# 2.net
KiCad netlist of a schematic drawn in Altium Designer
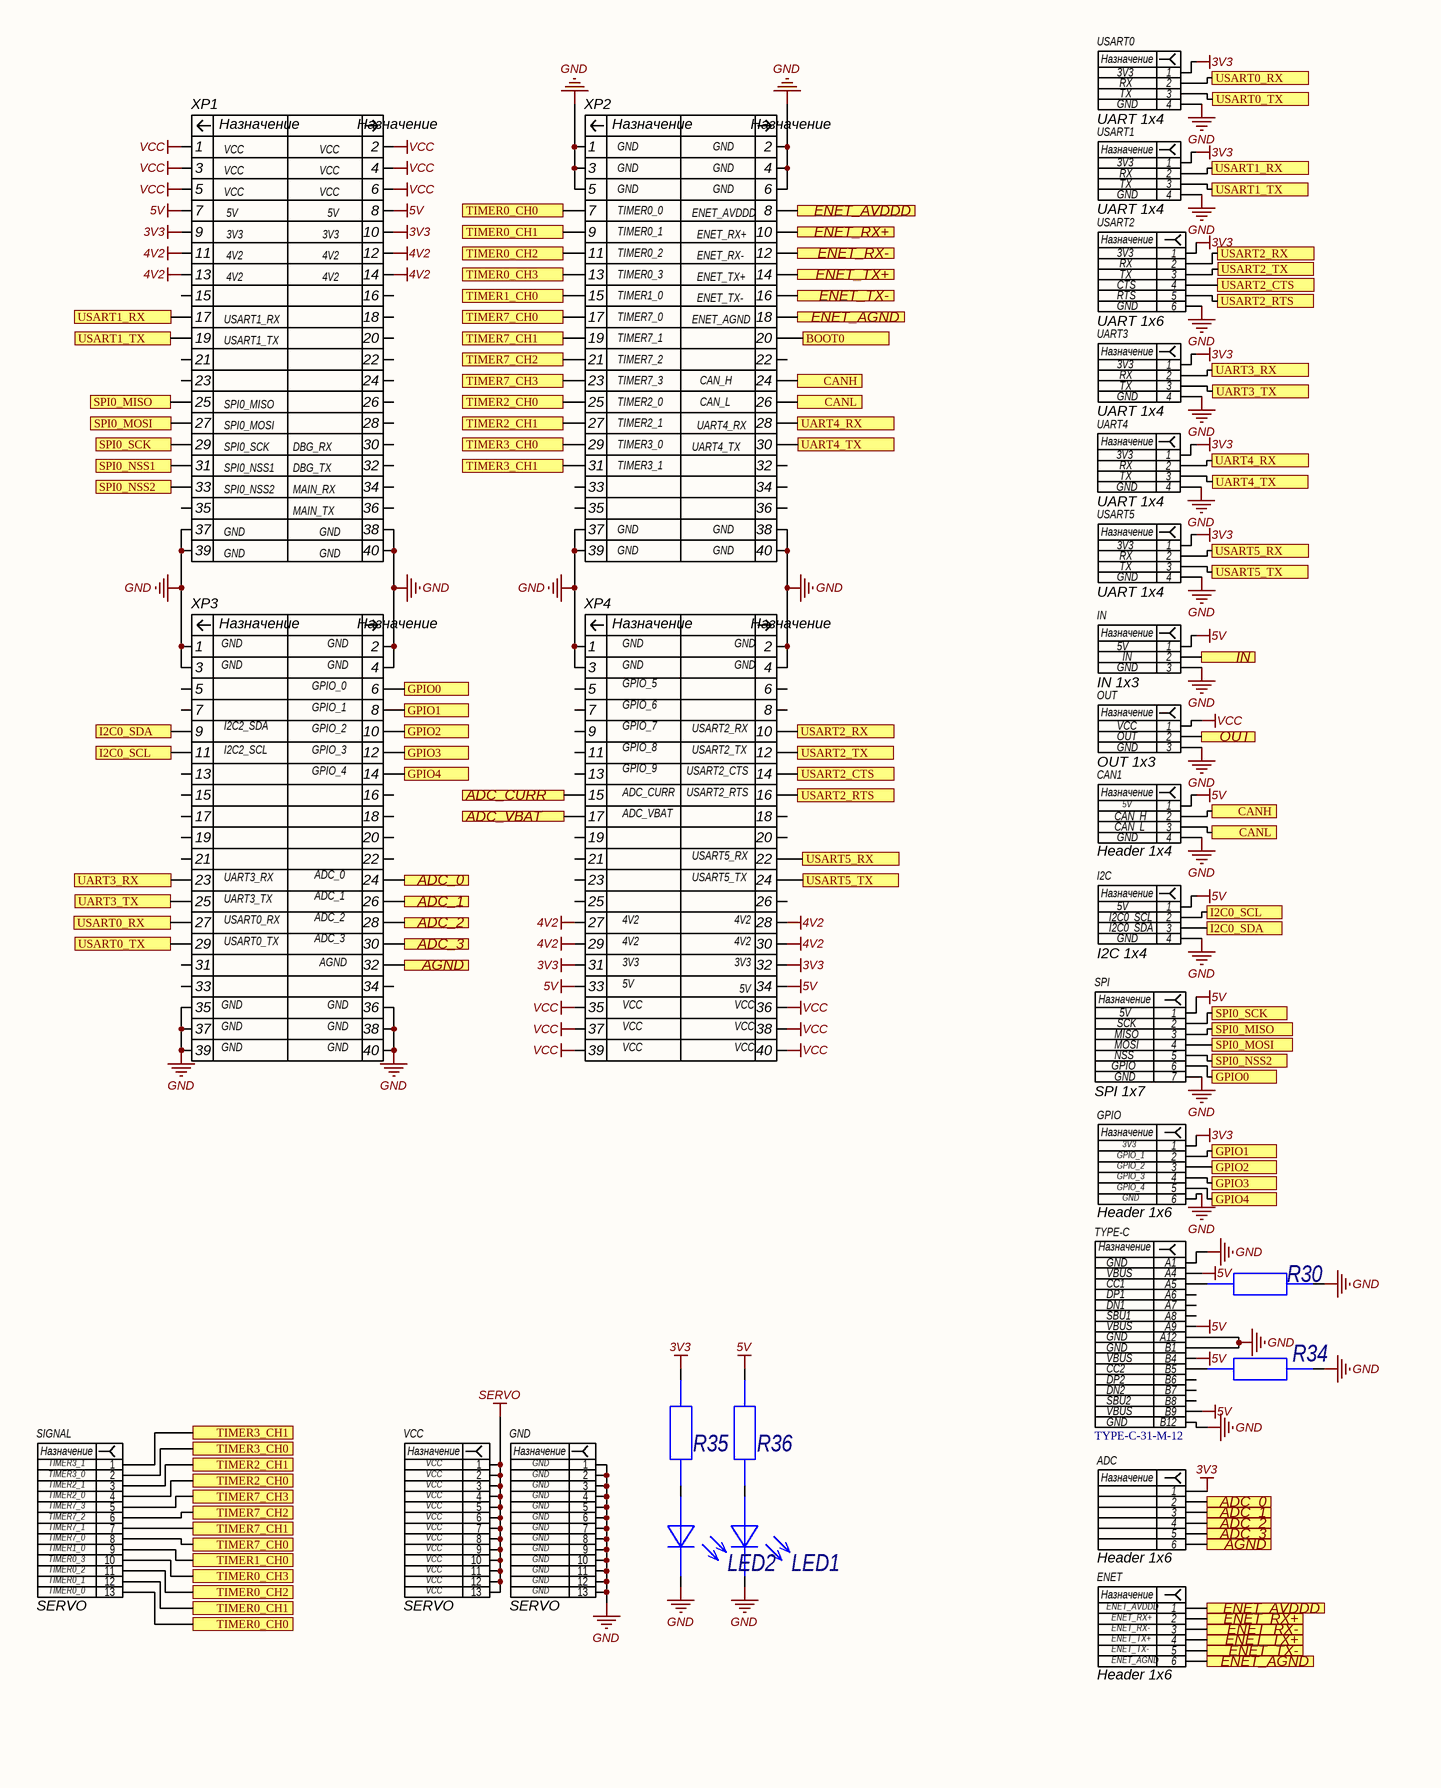
[diagram p0: нижняя плата версия 2.SchDoc, left]
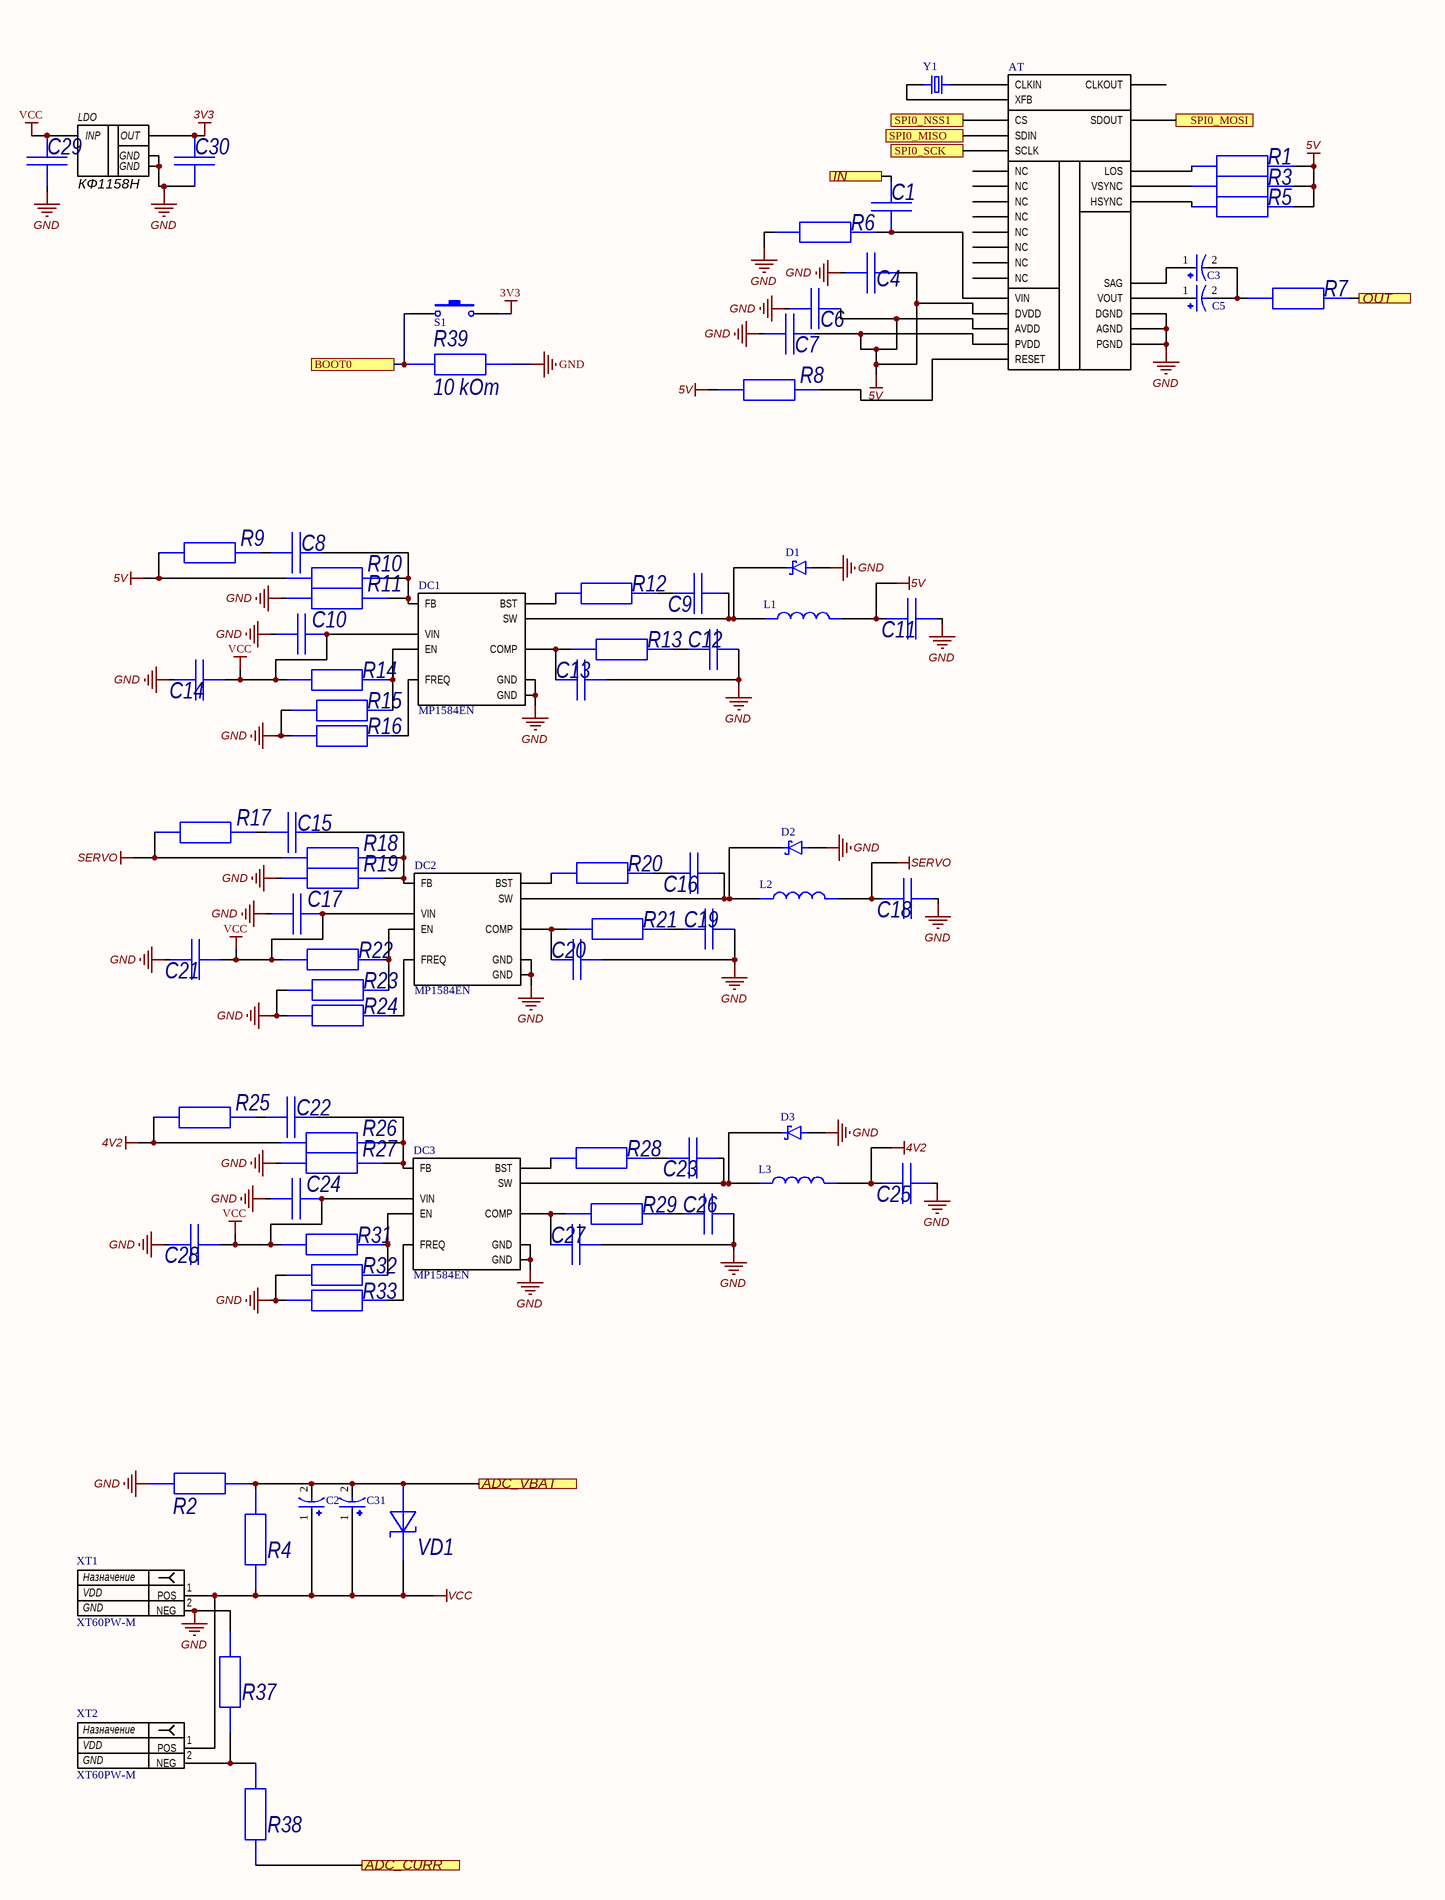
[diagram p1: нижняя плата версия 2.SchDoc, right]

(export (version "E")
  (design (tool "Eeschema 10.0.6"))
  (components
    (comp (ref "ADC")
      (value "Header 1x6")
      (footprint "PicoBlade 6pin")
      (libsource (lib "полётный контроллер") (part "Header 1x6"))
    )
    (comp (ref "AT")
      (value "AT7456")
      (footprint "at7456")
      (description "OSD")
      (libsource (lib "полётный контроллер") (part "AT7456"))
    )
    (comp (ref "C1")
      (value "Capacitor")
      (footprint "C0603")
      (fields (field (name "PUBLISHER") "Andrew Danich"))
      (libsource (lib "Capacitor GOST") (part "Capacitor"))
    )
    (comp (ref "C2")
      (value "T493B105K025BC6120")
      (footprint "CAPPM3528X210N")
      (description "Tantalum Surface Mount Capacitors")
      (fields (field (name "MF") "KEMET"))
      (libsource (lib "T493B105K025BC6120") (part "T493B105K025BC6120"))
    )
    (comp (ref "C3")
      (value "T493B105K025BC6120")
      (footprint "CAPPM3528X210N")
      (description "Tantalum Surface Mount Capacitors")
      (fields (field (name "MF") "KEMET"))
      (libsource (lib "") (part "T493B105K025BC6120_1"))
    )
    (comp (ref "C4")
      (value "Capacitor")
      (footprint "C0603")
      (fields (field (name "PUBLISHER") "Andrew Danich"))
      (libsource (lib "Capacitor GOST") (part "Capacitor"))
    )
    (comp (ref "C5")
      (value "T493B105K025BC6120")
      (footprint "CAPPM3528X210N")
      (description "Tantalum Surface Mount Capacitors")
      (fields (field (name "MF") "KEMET"))
      (libsource (lib "") (part "T493B105K025BC6120_1"))
    )
    (comp (ref "C6")
      (value "Capacitor")
      (footprint "C0603")
      (fields (field (name "PUBLISHER") "Andrew Danich"))
      (libsource (lib "Capacitor GOST") (part "Capacitor"))
    )
    (comp (ref "C7")
      (value "Capacitor")
      (footprint "C0603")
      (fields (field (name "PUBLISHER") "Andrew Danich"))
      (libsource (lib "Capacitor GOST") (part "Capacitor"))
    )
    (comp (ref "C8")
      (value "22 pF")
      (footprint "C0603")
      (fields (field (name "PUBLISHER") "Andrew Danich"))
      (libsource (lib "Capacitor GOST") (part "Capacitor"))
    )
    (comp (ref "C9")
      (value "0.1 uF")
      (footprint "C0603")
      (fields (field (name "PUBLISHER") "Andrew Danich"))
      (libsource (lib "Capacitor GOST") (part "Capacitor"))
    )
    (comp (ref "C10")
      (value "0.1 uF")
      (footprint "C0603")
      (fields (field (name "PUBLISHER") "Andrew Danich"))
      (libsource (lib "Capacitor GOST") (part "Capacitor"))
    )
    (comp (ref "C11")
      (value "22 uF")
      (footprint "C0603")
      (fields (field (name "PUBLISHER") "Andrew Danich"))
      (libsource (lib "Capacitor GOST") (part "Capacitor"))
    )
    (comp (ref "C12")
      (value "330 pF")
      (footprint "C0603")
      (fields (field (name "PUBLISHER") "Andrew Danich"))
      (libsource (lib "Capacitor GOST") (part "Capacitor"))
    )
    (comp (ref "C13")
      (value "1 pF")
      (footprint "C0603")
      (fields (field (name "PUBLISHER") "Andrew Danich"))
      (libsource (lib "Capacitor GOST") (part "Capacitor"))
    )
    (comp (ref "C14")
      (value "4.7 uF")
      (footprint "C0603")
      (fields (field (name "PUBLISHER") "Andrew Danich"))
      (libsource (lib "Capacitor GOST") (part "Capacitor"))
    )
    (comp (ref "C15")
      (value "22 pF")
      (footprint "C0603")
      (fields (field (name "PUBLISHER") "Andrew Danich"))
      (libsource (lib "Capacitor GOST") (part "Capacitor"))
    )
    (comp (ref "C16")
      (value "0.1 uF")
      (footprint "C0603")
      (fields (field (name "PUBLISHER") "Andrew Danich"))
      (libsource (lib "Capacitor GOST") (part "Capacitor"))
    )
    (comp (ref "C17")
      (value "0.1 uF")
      (footprint "C0603")
      (fields (field (name "PUBLISHER") "Andrew Danich"))
      (libsource (lib "Capacitor GOST") (part "Capacitor"))
    )
    (comp (ref "C18")
      (value "22 uF")
      (footprint "C0603")
      (fields (field (name "PUBLISHER") "Andrew Danich"))
      (libsource (lib "Capacitor GOST") (part "Capacitor"))
    )
    (comp (ref "C19")
      (value "330 pF")
      (footprint "C0603")
      (fields (field (name "PUBLISHER") "Andrew Danich"))
      (libsource (lib "Capacitor GOST") (part "Capacitor"))
    )
    (comp (ref "C20")
      (value "1 pF")
      (footprint "C0603")
      (fields (field (name "PUBLISHER") "Andrew Danich"))
      (libsource (lib "Capacitor GOST") (part "Capacitor"))
    )
    (comp (ref "C21")
      (value "4.7 uF")
      (footprint "C0603")
      (fields (field (name "PUBLISHER") "Andrew Danich"))
      (libsource (lib "Capacitor GOST") (part "Capacitor"))
    )
    (comp (ref "C22")
      (value "22 pF")
      (footprint "C0603")
      (fields (field (name "PUBLISHER") "Andrew Danich"))
      (libsource (lib "Capacitor GOST") (part "Capacitor"))
    )
    (comp (ref "C23")
      (value "0.1 uF")
      (footprint "C0603")
      (fields (field (name "PUBLISHER") "Andrew Danich"))
      (libsource (lib "Capacitor GOST") (part "Capacitor"))
    )
    (comp (ref "C24")
      (value "0.1 uF")
      (footprint "C0603")
      (fields (field (name "PUBLISHER") "Andrew Danich"))
      (libsource (lib "Capacitor GOST") (part "Capacitor"))
    )
    (comp (ref "C25")
      (value "33 uF")
      (footprint "C0603")
      (fields (field (name "PUBLISHER") "Andrew Danich"))
      (libsource (lib "Capacitor GOST") (part "Capacitor"))
    )
    (comp (ref "C26")
      (value "330 pF")
      (footprint "C0603")
      (fields (field (name "PUBLISHER") "Andrew Danich"))
      (libsource (lib "Capacitor GOST") (part "Capacitor"))
    )
    (comp (ref "C27")
      (value "2 pF")
      (footprint "C0603")
      (fields (field (name "PUBLISHER") "Andrew Danich"))
      (libsource (lib "Capacitor GOST") (part "Capacitor"))
    )
    (comp (ref "C28")
      (value "4.7 uF")
      (footprint "C0603")
      (fields (field (name "PUBLISHER") "Andrew Danich"))
      (libsource (lib "Capacitor GOST") (part "Capacitor"))
    )
    (comp (ref "C29")
      (value "0.1 uF")
      (footprint "C0603")
      (fields (field (name "PUBLISHER") "Andrew Danich"))
      (libsource (lib "Capacitor GOST") (part "Capacitor"))
    )
    (comp (ref "C30")
      (value "10 uF")
      (footprint "C0603")
      (fields (field (name "PUBLISHER") "Andrew Danich"))
      (libsource (lib "Capacitor GOST") (part "Capacitor"))
    )
    (comp (ref "C31")
      (value "T493B105K025BC6120")
      (footprint "CAPPM3528X210N")
      (description "Tantalum Surface Mount Capacitors")
      (fields (field (name "MF") "KEMET"))
      (libsource (lib "T493B105K025BC6120") (part "T493B105K025BC6120"))
    )
    (comp (ref "CAN1")
      (value "Header 1x4")
      (footprint "PicoBlade 4pin")
      (libsource (lib "полётный контроллер") (part "Header 1x4"))
    )
    (comp (ref "D1")
      (value "B340A-13-F")
      (footprint "DIOM5226X240N")
      (description "Diode, Rectifier, 3a, 40v, Do-214ac, Full Reel")
      (libsource (lib "B340A-13-F") (part "B340A-13-F"))
    )
    (comp (ref "D2")
      (value "B340A-13-F")
      (footprint "DIOM5226X240N")
      (description "Diode, Rectifier, 3a, 40v, Do-214ac, Full Reel")
      (libsource (lib "B340A-13-F") (part "B340A-13-F"))
    )
    (comp (ref "D3")
      (value "B340A-13-F")
      (footprint "DIOM5226X240N")
      (description "Diode, Rectifier, 3a, 40v, Do-214ac, Full Reel")
      (libsource (lib "B340A-13-F") (part "B340A-13-F"))
    )
    (comp (ref "DC1")
      (value "MP1584EN")
      (footprint "SOIC127P600X170-9N")
      (libsource (lib "полётный контроллер") (part "MP1584EN"))
    )
    (comp (ref "DC2")
      (value "MP1584EN")
      (footprint "SOIC127P600X170-9N")
      (libsource (lib "полётный контроллер") (part "MP1584EN"))
    )
    (comp (ref "DC3")
      (value "MP1584EN")
      (footprint "SOIC127P600X170-9N")
      (libsource (lib "полётный контроллер") (part "MP1584EN"))
    )
    (comp (ref "ENET")
      (value "Header 1x6")
      (footprint "PicoBlade 6pin")
      (libsource (lib "полётный контроллер") (part "Header 1x6"))
    )
    (comp (ref "GND")
      (value "SERVO")
      (footprint "SERV")
      (libsource (lib "полётный контроллер") (part "SERVO"))
    )
    (comp (ref "GPIO")
      (value "Header 1x6")
      (footprint "PicoBlade 6pin")
      (libsource (lib "полётный контроллер") (part "Header 1x6"))
    )
    (comp (ref "I2C")
      (value "I2C 1x4")
      (footprint "PicoBlade 4pin")
      (libsource (lib "полётный контроллер") (part "I2C 1x4"))
    )
    (comp (ref "IN")
      (value "IN 1x3")
      (footprint "PicoBlade 3pin")
      (libsource (lib "полётный контроллер") (part "IN 1x3"))
    )
    (comp (ref "L1")
      (value "12.3 uH")
      (footprint "IND_VLS6045EX-150M")
      (description "15 ÂµH Shielded Drum Core, Wirewound Inductor 2.5 A 75mOhm Nonstandard")
      (fields (field (name "MF") "TDK") (field (name "MP") "VLS6045EX-150M"))
      (libsource (lib "VLS6045EX-150M") (part "VLS6045EX-150M"))
    )
    (comp (ref "L2")
      (value "12.3 uH")
      (footprint "IND_VLS6045EX-150M")
      (description "15 ÂµH Shielded Drum Core, Wirewound Inductor 2.5 A 75mOhm Nonstandard")
      (fields (field (name "MF") "TDK") (field (name "MP") "VLS6045EX-150M"))
      (libsource (lib "VLS6045EX-150M") (part "VLS6045EX-150M"))
    )
    (comp (ref "L3")
      (value "12.3 uH")
      (footprint "IND_VLS6045EX-150M")
      (description "15 ÂµH Shielded Drum Core, Wirewound Inductor 2.5 A 75mOhm Nonstandard")
      (fields (field (name "MF") "TDK") (field (name "MP") "VLS6045EX-150M"))
      (libsource (lib "VLS6045EX-150M") (part "VLS6045EX-150M"))
    )
    (comp (ref "LDO")
      (value "КФ1158Н")
      (footprint "ТО-263")
      (libsource (lib "полётный контроллер") (part "КФ1158Н"))
    )
    (comp (ref "LED1")
      (value "Text")
      (footprint "LD0805")
      (fields (field (name "PUBLISHER") "Andrew Danich"))
      (libsource (lib "Led GOST") (part "Led-1"))
    )
    (comp (ref "LED2")
      (value "Text")
      (footprint "LD0805")
      (fields (field (name "PUBLISHER") "Andrew Danich"))
      (libsource (lib "Led GOST") (part "Led-1"))
    )
    (comp (ref "OUT")
      (value "OUT 1x3")
      (footprint "PicoBlade 3pin")
      (libsource (lib "полётный контроллер") (part "OUT 1x3"))
    )
    (comp (ref "R1")
      (value "1 kOm")
      (footprint "R0603")
      (fields (field (name "PUBLISHER") "Andrew Danich"))
      (libsource (lib "Resistor GOST") (part "Resistor"))
    )
    (comp (ref "R2")
      (value "~")
      (footprint "R0603")
      (fields (field (name "PUBLISHER") "Andrew Danich"))
      (libsource (lib "Resistor GOST") (part "Resistor"))
    )
    (comp (ref "R3")
      (value "1 kOm")
      (footprint "R0603")
      (fields (field (name "PUBLISHER") "Andrew Danich"))
      (libsource (lib "Resistor GOST") (part "Resistor"))
    )
    (comp (ref "R4")
      (value "~")
      (footprint "R0603")
      (fields (field (name "PUBLISHER") "Andrew Danich"))
      (libsource (lib "Resistor GOST") (part "Resistor"))
    )
    (comp (ref "R5")
      (value "1 kOm")
      (footprint "R0603")
      (fields (field (name "PUBLISHER") "Andrew Danich"))
      (libsource (lib "Resistor GOST") (part "Resistor"))
    )
    (comp (ref "R6")
      (value "10 kOm")
      (footprint "R0603")
      (fields (field (name "PUBLISHER") "Andrew Danich"))
      (libsource (lib "Resistor GOST") (part "Resistor"))
    )
    (comp (ref "R7")
      (value "10 kOm")
      (footprint "R0603")
      (fields (field (name "PUBLISHER") "Andrew Danich"))
      (libsource (lib "Resistor GOST") (part "Resistor"))
    )
    (comp (ref "R8")
      (value "10 kOm")
      (footprint "R0603")
      (fields (field (name "PUBLISHER") "Andrew Danich"))
      (libsource (lib "Resistor GOST") (part "Resistor"))
    )
    (comp (ref "R9")
      (value "0")
      (footprint "R0603")
      (fields (field (name "PUBLISHER") "Andrew Danich"))
      (libsource (lib "Resistor GOST") (part "Resistor"))
    )
    (comp (ref "R10")
      (value "124 kOm")
      (footprint "R0603")
      (fields (field (name "PUBLISHER") "Andrew Danich"))
      (libsource (lib "Resistor GOST") (part "Resistor"))
    )
    (comp (ref "R11")
      (value "23.7 kOm")
      (footprint "R0603")
      (fields (field (name "PUBLISHER") "Andrew Danich"))
      (libsource (lib "Resistor GOST") (part "Resistor"))
    )
    (comp (ref "R12")
      (value "0")
      (footprint "R0603")
      (fields (field (name "PUBLISHER") "Andrew Danich"))
      (libsource (lib "Resistor GOST") (part "Resistor"))
    )
    (comp (ref "R13")
      (value "76.8 kOm")
      (footprint "R0603")
      (fields (field (name "PUBLISHER") "Andrew Danich"))
      (libsource (lib "Resistor GOST") (part "Resistor"))
    )
    (comp (ref "R14")
      (value "100 kOm")
      (footprint "R0603")
      (fields (field (name "PUBLISHER") "Andrew Danich"))
      (libsource (lib "Resistor GOST") (part "Resistor"))
    )
    (comp (ref "R15")
      (value "18.7 kOm")
      (footprint "R0603")
      (fields (field (name "PUBLISHER") "Andrew Danich"))
      (libsource (lib "Resistor GOST") (part "Resistor"))
    )
    (comp (ref "R16")
      (value "193.38 kOm")
      (footprint "R0603")
      (fields (field (name "PUBLISHER") "Andrew Danich"))
      (libsource (lib "Resistor GOST") (part "Resistor"))
    )
    (comp (ref "R17")
      (value "0")
      (footprint "R0603")
      (fields (field (name "PUBLISHER") "Andrew Danich"))
      (libsource (lib "Resistor GOST") (part "Resistor"))
    )
    (comp (ref "R18")
      (value "124 kOm")
      (footprint "R0603")
      (fields (field (name "PUBLISHER") "Andrew Danich"))
      (libsource (lib "Resistor GOST") (part "Resistor"))
    )
    (comp (ref "R19")
      (value "23.7 kOm")
      (footprint "R0603")
      (fields (field (name "PUBLISHER") "Andrew Danich"))
      (libsource (lib "Resistor GOST") (part "Resistor"))
    )
    (comp (ref "R20")
      (value "0")
      (footprint "R0603")
      (fields (field (name "PUBLISHER") "Andrew Danich"))
      (libsource (lib "Resistor GOST") (part "Resistor"))
    )
    (comp (ref "R21")
      (value "76.8 kOm")
      (footprint "R0603")
      (fields (field (name "PUBLISHER") "Andrew Danich"))
      (libsource (lib "Resistor GOST") (part "Resistor"))
    )
    (comp (ref "R22")
      (value "100 kOm")
      (footprint "R0603")
      (fields (field (name "PUBLISHER") "Andrew Danich"))
      (libsource (lib "Resistor GOST") (part "Resistor"))
    )
    (comp (ref "R23")
      (value "18.7 kOm")
      (footprint "R0603")
      (fields (field (name "PUBLISHER") "Andrew Danich"))
      (libsource (lib "Resistor GOST") (part "Resistor"))
    )
    (comp (ref "R24")
      (value "193.38 kOm")
      (footprint "R0603")
      (fields (field (name "PUBLISHER") "Andrew Danich"))
      (libsource (lib "Resistor GOST") (part "Resistor"))
    )
    (comp (ref "R25")
      (value "0")
      (footprint "R0603")
      (fields (field (name "PUBLISHER") "Andrew Danich"))
      (libsource (lib "Resistor GOST") (part "Resistor"))
    )
    (comp (ref "R26")
      (value "124 kOm")
      (footprint "R0603")
      (fields (field (name "PUBLISHER") "Andrew Danich"))
      (libsource (lib "Resistor GOST") (part "Resistor"))
    )
    (comp (ref "R27")
      (value "29 kOm")
      (footprint "R0603")
      (fields (field (name "PUBLISHER") "Andrew Danich"))
      (libsource (lib "Resistor GOST") (part "Resistor"))
    )
    (comp (ref "R28")
      (value "0")
      (footprint "R0603")
      (fields (field (name "PUBLISHER") "Andrew Danich"))
      (libsource (lib "Resistor GOST") (part "Resistor"))
    )
    (comp (ref "R29")
      (value "100 kOm")
      (footprint "R0603")
      (fields (field (name "PUBLISHER") "Andrew Danich"))
      (libsource (lib "Resistor GOST") (part "Resistor"))
    )
    (comp (ref "R30")
      (value "10 kOm")
      (footprint "R0603")
      (fields (field (name "PUBLISHER") "Andrew Danich"))
      (libsource (lib "Resistor GOST") (part "Resistor"))
    )
    (comp (ref "R31")
      (value "100 kOm")
      (footprint "R0603")
      (fields (field (name "PUBLISHER") "Andrew Danich"))
      (libsource (lib "Resistor GOST") (part "Resistor"))
    )
    (comp (ref "R32")
      (value "18.7 kOm")
      (footprint "R0603")
      (fields (field (name "PUBLISHER") "Andrew Danich"))
      (libsource (lib "Resistor GOST") (part "Resistor"))
    )
    (comp (ref "R33")
      (value "193.38 kOm")
      (footprint "R0603")
      (fields (field (name "PUBLISHER") "Andrew Danich"))
      (libsource (lib "Resistor GOST") (part "Resistor"))
    )
    (comp (ref "R34")
      (value "10 kOm")
      (footprint "R0603")
      (fields (field (name "PUBLISHER") "Andrew Danich"))
      (libsource (lib "Resistor GOST") (part "Resistor"))
    )
    (comp (ref "R35")
      (value "10 kOm")
      (footprint "R0603")
      (fields (field (name "PUBLISHER") "Andrew Danich"))
      (libsource (lib "Resistor GOST") (part "Resistor"))
    )
    (comp (ref "R36")
      (value "10 kOm")
      (footprint "R0603")
      (fields (field (name "PUBLISHER") "Andrew Danich"))
      (libsource (lib "Resistor GOST") (part "Resistor"))
    )
    (comp (ref "R37")
      (value "~")
      (footprint "R2512")
      (fields (field (name "PUBLISHER") "Andrew Danich"))
      (libsource (lib "Resistor GOST") (part "Resistor"))
    )
    (comp (ref "R38")
      (value "~")
      (footprint "R0603")
      (fields (field (name "PUBLISHER") "Andrew Danich"))
      (libsource (lib "Resistor GOST") (part "Resistor"))
    )
    (comp (ref "R39")
      (value "10 kOm")
      (footprint "R0603")
      (fields (field (name "PUBLISHER") "Andrew Danich"))
      (libsource (lib "Resistor GOST") (part "Resistor"))
    )
    (comp (ref "S1")
      (value "SW-PB")
      (footprint "SWIT")
      (description "Switch")
      (fields (field (name "PUBLISHER") "Altium Limited"))
      (libsource (lib "Miscellaneous Devices") (part "SW-PB"))
    )
    (comp (ref "SIGNAL")
      (value "SERVO")
      (footprint "SERV")
      (libsource (lib "полётный контроллер") (part "SERVO"))
    )
    (comp (ref "SPI")
      (value "SPI 1x7")
      (footprint "PicoBlade 7pin")
      (libsource (lib "полётный контроллер") (part "SPI 1x7"))
    )
    (comp (ref "TYPE-C")
      (value "TYPE-C-31-M-12")
      (footprint "HRO_TYPE-C-31-M-12")
      (libsource (lib "полётный контроллер") (part "TYPE-C-31-M-12"))
    )
    (comp (ref "UART3")
      (value "UART 1x4")
      (footprint "PicoBlade 4pin")
      (libsource (lib "полётный контроллер") (part "UART 1x4"))
    )
    (comp (ref "UART4")
      (value "UART 1x4")
      (footprint "PicoBlade 4pin")
      (libsource (lib "полётный контроллер") (part "UART 1x4"))
    )
    (comp (ref "USART0")
      (value "UART 1x4")
      (footprint "PicoBlade 4pin")
      (libsource (lib "полётный контроллер") (part "UART 1x4"))
    )
    (comp (ref "USART1")
      (value "UART 1x4")
      (footprint "PicoBlade 4pin")
      (libsource (lib "полётный контроллер") (part "UART 1x4"))
    )
    (comp (ref "USART2")
      (value "UART 1x6")
      (footprint "PicoBlade 6pin")
      (libsource (lib "полётный контроллер") (part "UART 1x6"))
    )
    (comp (ref "USART5")
      (value "UART 1x4")
      (footprint "PicoBlade 4pin")
      (libsource (lib "полётный контроллер") (part "UART 1x4"))
    )
    (comp (ref "VCC")
      (value "SERVO")
      (footprint "SERV")
      (libsource (lib "полётный контроллер") (part "SERVO"))
    )
    (comp (ref "VD1")
      (value "Schottky")
      (footprint "DO-214AA")
      (fields (field (name "PUBLISHER") "Andrew Danich"))
      (libsource (lib "Diode GOST") (part "Schottky"))
    )
    (comp (ref "XP1")
      (value "PLLD-1.27-40S")
      (footprint "Headr 2x20 male")
      (libsource (lib "Разьемы_PLLD_PBD") (part "PLLD-1.27-40S"))
    )
    (comp (ref "XP2")
      (value "PLLD-1.27-40S")
      (footprint "Headr 2x20 male")
      (libsource (lib "Разьемы_PLLD_PBD") (part "PLLD-1.27-40S"))
    )
    (comp (ref "XP3")
      (value "PLLD-1.27-40S")
      (footprint "Headr 2x20 male")
      (libsource (lib "Разьемы_PLLD_PBD") (part "PLLD-1.27-40S"))
    )
    (comp (ref "XP4")
      (value "PLLD-1.27-40S")
      (footprint "Headr 2x20 male")
      (libsource (lib "Разьемы_PLLD_PBD") (part "PLLD-1.27-40S"))
    )
    (comp (ref "XT1")
      (value "XT60PW-M")
      (footprint "AMASS_XT60PW-M")
      (libsource (lib "полётный контроллер") (part "XT60PW-M"))
    )
    (comp (ref "XT2")
      (value "XT60PW-M")
      (footprint "AMASS_XT60PW-M")
      (libsource (lib "полётный контроллер") (part "XT60PW-M"))
    )
    (comp (ref "Y1")
      (value "ABM7-8.000MHZ-8-R80-D2Y-T")
      (footprint "XTAL_ABM7-8.000MHZ-8-R80-D2Y-T")
      (description "Crystal 22.1184MHz Ã‚Â±20ppm (Tol) Ã‚Â±30ppm (Stability) 18pF FUND 50Ohm 2-Pin Mini-CSMD T/R")
      (libsource (lib "ABM7-8.000MHZ-8-R80-D2Y-T") (part "ABM7-8.000MHZ-8-R80-D2Y-T"))
    )
  )
  (nets
    (net (code "1") (name "/ADC_0") (class "Default")
      (node (ref "ADC") (pin "2") (pinfunction "2_2") (pintype "passive"))
      (node (ref "XP3") (pin "24") (pinfunction "24_24") (pintype "passive"))
    )
    (net (code "2") (name "/ADC_1") (class "Default")
      (node (ref "ADC") (pin "3") (pinfunction "3_3") (pintype "passive"))
      (node (ref "XP3") (pin "26") (pinfunction "26_26") (pintype "passive"))
    )
    (net (code "3") (name "/ADC_2") (class "Default")
      (node (ref "ADC") (pin "4") (pinfunction "4_4") (pintype "passive"))
      (node (ref "XP3") (pin "28") (pinfunction "28_28") (pintype "passive"))
    )
    (net (code "4") (name "/ADC_3") (class "Default")
      (node (ref "ADC") (pin "5") (pinfunction "5_5") (pintype "passive"))
      (node (ref "XP3") (pin "30") (pinfunction "30_30") (pintype "passive"))
    )
    (net (code "5") (name "/ADC_CURR") (class "Default")
      (node (ref "R38") (pin "1") (pinfunction "1_1") (pintype "passive"))
      (node (ref "XP4") (pin "15") (pinfunction "15_15") (pintype "passive"))
    )
    (net (code "6") (name "/ADC_VBAT") (class "Default")
      (node (ref "C2") (pin "2") (pinfunction "2_2") (pintype "passive"))
      (node (ref "C31") (pin "2") (pinfunction "2_2") (pintype "passive"))
      (node (ref "R2") (pin "1") (pinfunction "1_1") (pintype "passive"))
      (node (ref "R4") (pin "1") (pinfunction "1_1") (pintype "passive"))
      (node (ref "VD1") (pin "1") (pinfunction "А_1") (pintype "passive"))
      (node (ref "XP4") (pin "17") (pinfunction "17_17") (pintype "passive"))
    )
    (net (code "7") (name "/AGND") (class "Default")
      (node (ref "ADC") (pin "6") (pinfunction "6_6") (pintype "passive"))
      (node (ref "XP3") (pin "32") (pinfunction "32_32") (pintype "passive"))
    )
    (net (code "8") (name "/BOOT0") (class "Default")
      (node (ref "R39") (pin "2") (pinfunction "2_2") (pintype "passive"))
      (node (ref "S1") (pin "1") (pinfunction "1_1") (pintype "passive"))
      (node (ref "XP2") (pin "20") (pinfunction "20_20") (pintype "passive"))
    )
    (net (code "9") (name "/CANH") (class "Default")
      (node (ref "CAN1") (pin "2") (pinfunction "2_2") (pintype "passive"))
      (node (ref "XP2") (pin "24") (pinfunction "24_24") (pintype "passive"))
    )
    (net (code "10") (name "/CANL") (class "Default")
      (node (ref "CAN1") (pin "3") (pinfunction "3_3") (pintype "passive"))
      (node (ref "XP2") (pin "26") (pinfunction "26_26") (pintype "passive"))
    )
    (net (code "11") (name "/ENET_AGND") (class "Default")
      (node (ref "ENET") (pin "6") (pinfunction "6_6") (pintype "passive"))
      (node (ref "XP2") (pin "18") (pinfunction "18_18") (pintype "passive"))
    )
    (net (code "12") (name "/ENET_AVDDD") (class "Default")
      (node (ref "ENET") (pin "1") (pinfunction "1_1") (pintype "passive"))
      (node (ref "XP2") (pin "8") (pinfunction "8_8") (pintype "passive"))
    )
    (net (code "13") (name "/ENET_RX+") (class "Default")
      (node (ref "ENET") (pin "2") (pinfunction "2_2") (pintype "passive"))
      (node (ref "XP2") (pin "10") (pinfunction "10_10") (pintype "passive"))
    )
    (net (code "14") (name "/ENET_RX-") (class "Default")
      (node (ref "ENET") (pin "3") (pinfunction "3_3") (pintype "passive"))
      (node (ref "XP2") (pin "12") (pinfunction "12_12") (pintype "passive"))
    )
    (net (code "15") (name "/ENET_TX+") (class "Default")
      (node (ref "ENET") (pin "4") (pinfunction "4_4") (pintype "passive"))
      (node (ref "XP2") (pin "14") (pinfunction "14_14") (pintype "passive"))
    )
    (net (code "16") (name "/ENET_TX-") (class "Default")
      (node (ref "ENET") (pin "5") (pinfunction "5_5") (pintype "passive"))
      (node (ref "XP2") (pin "16") (pinfunction "16_16") (pintype "passive"))
    )
    (net (code "17") (name "/GPIO0") (class "Default")
      (node (ref "SPI") (pin "6") (pinfunction "6_6") (pintype "passive"))
      (node (ref "XP3") (pin "6") (pinfunction "6_6") (pintype "passive"))
    )
    (net (code "18") (name "/GPIO1") (class "Default")
      (node (ref "GPIO") (pin "2") (pinfunction "2_2") (pintype "passive"))
      (node (ref "XP3") (pin "8") (pinfunction "8_8") (pintype "passive"))
    )
    (net (code "19") (name "/GPIO2") (class "Default")
      (node (ref "GPIO") (pin "3") (pinfunction "3_3") (pintype "passive"))
      (node (ref "XP3") (pin "10") (pinfunction "10_10") (pintype "passive"))
    )
    (net (code "20") (name "/GPIO3") (class "Default")
      (node (ref "GPIO") (pin "4") (pinfunction "4_4") (pintype "passive"))
      (node (ref "XP3") (pin "12") (pinfunction "12_12") (pintype "passive"))
    )
    (net (code "21") (name "/GPIO4") (class "Default")
      (node (ref "GPIO") (pin "5") (pinfunction "5_5") (pintype "passive"))
      (node (ref "XP3") (pin "14") (pinfunction "14_14") (pintype "passive"))
    )
    (net (code "22") (name "/I2C0_SCL") (class "Default")
      (node (ref "I2C") (pin "2") (pinfunction "2_2") (pintype "passive"))
      (node (ref "XP3") (pin "11") (pinfunction "11_11") (pintype "passive"))
    )
    (net (code "23") (name "/I2C0_SDA") (class "Default")
      (node (ref "I2C") (pin "3") (pinfunction "3_3") (pintype "passive"))
      (node (ref "XP3") (pin "9") (pinfunction "9_9") (pintype "passive"))
    )
    (net (code "24") (name "/IN") (class "Default")
      (node (ref "C1") (pin "2") (pinfunction "2_2") (pintype "passive"))
      (node (ref "IN") (pin "2") (pinfunction "2_2") (pintype "passive"))
    )
    (net (code "25") (name "/OUT") (class "Default")
      (node (ref "OUT") (pin "2") (pinfunction "2_2") (pintype "passive"))
      (node (ref "R7") (pin "2") (pinfunction "2_2") (pintype "passive"))
    )
    (net (code "26") (name "/SPI0_MISO") (class "Default")
      (node (ref "AT") (pin "9") (pinfunction "SDIN_9") (pintype "passive"))
      (node (ref "SPI") (pin "3") (pinfunction "3_3") (pintype "passive"))
      (node (ref "XP1") (pin "25") (pinfunction "25_25") (pintype "passive"))
    )
    (net (code "27") (name "/SPI0_MOSI") (class "Default")
      (node (ref "AT") (pin "11") (pinfunction "SDOUT_11") (pintype "passive"))
      (node (ref "SPI") (pin "4") (pinfunction "4_4") (pintype "passive"))
      (node (ref "XP1") (pin "27") (pinfunction "27_27") (pintype "passive"))
    )
    (net (code "28") (name "/SPI0_NSS1") (class "Default")
      (node (ref "AT") (pin "8") (pinfunction "CS_8") (pintype "passive"))
      (node (ref "XP1") (pin "31") (pinfunction "31_31") (pintype "passive"))
    )
    (net (code "29") (name "/SPI0_NSS2") (class "Default")
      (node (ref "SPI") (pin "5") (pinfunction "5_5") (pintype "passive"))
      (node (ref "XP1") (pin "33") (pinfunction "33_33") (pintype "passive"))
    )
    (net (code "30") (name "/SPI0_SCK") (class "Default")
      (node (ref "AT") (pin "10") (pinfunction "SCLK_10") (pintype "passive"))
      (node (ref "SPI") (pin "2") (pinfunction "2_2") (pintype "passive"))
      (node (ref "XP1") (pin "29") (pinfunction "29_29") (pintype "passive"))
    )
    (net (code "31") (name "/TIMER0_CH0") (class "Default")
      (node (ref "SIGNAL") (pin "13") (pinfunction "13_13") (pintype "passive"))
      (node (ref "XP2") (pin "7") (pinfunction "7_7") (pintype "passive"))
    )
    (net (code "32") (name "/TIMER0_CH1") (class "Default")
      (node (ref "SIGNAL") (pin "12") (pinfunction "12_12") (pintype "passive"))
      (node (ref "XP2") (pin "9") (pinfunction "9_9") (pintype "passive"))
    )
    (net (code "33") (name "/TIMER0_CH2") (class "Default")
      (node (ref "SIGNAL") (pin "11") (pinfunction "11_11") (pintype "passive"))
      (node (ref "XP2") (pin "11") (pinfunction "11_11") (pintype "passive"))
    )
    (net (code "34") (name "/TIMER0_CH3") (class "Default")
      (node (ref "SIGNAL") (pin "10") (pinfunction "10_10") (pintype "passive"))
      (node (ref "XP2") (pin "13") (pinfunction "13_13") (pintype "passive"))
    )
    (net (code "35") (name "/TIMER1_CH0") (class "Default")
      (node (ref "SIGNAL") (pin "9") (pinfunction "9_9") (pintype "passive"))
      (node (ref "XP2") (pin "15") (pinfunction "15_15") (pintype "passive"))
    )
    (net (code "36") (name "/TIMER2_CH0") (class "Default")
      (node (ref "SIGNAL") (pin "4") (pinfunction "4_4") (pintype "passive"))
      (node (ref "XP2") (pin "25") (pinfunction "25_25") (pintype "passive"))
    )
    (net (code "37") (name "/TIMER2_CH1") (class "Default")
      (node (ref "SIGNAL") (pin "3") (pinfunction "3_3") (pintype "passive"))
      (node (ref "XP2") (pin "27") (pinfunction "27_27") (pintype "passive"))
    )
    (net (code "38") (name "/TIMER3_CH0") (class "Default")
      (node (ref "SIGNAL") (pin "2") (pinfunction "2_2") (pintype "passive"))
      (node (ref "XP2") (pin "29") (pinfunction "29_29") (pintype "passive"))
    )
    (net (code "39") (name "/TIMER3_CH1") (class "Default")
      (node (ref "SIGNAL") (pin "1") (pinfunction "1_1") (pintype "passive"))
      (node (ref "XP2") (pin "31") (pinfunction "31_31") (pintype "passive"))
    )
    (net (code "40") (name "/TIMER7_CH0") (class "Default")
      (node (ref "SIGNAL") (pin "8") (pinfunction "8_8") (pintype "passive"))
      (node (ref "XP2") (pin "17") (pinfunction "17_17") (pintype "passive"))
    )
    (net (code "41") (name "/TIMER7_CH1") (class "Default")
      (node (ref "SIGNAL") (pin "7") (pinfunction "7_7") (pintype "passive"))
      (node (ref "XP2") (pin "19") (pinfunction "19_19") (pintype "passive"))
    )
    (net (code "42") (name "/TIMER7_CH2") (class "Default")
      (node (ref "SIGNAL") (pin "6") (pinfunction "6_6") (pintype "passive"))
      (node (ref "XP2") (pin "21") (pinfunction "21_21") (pintype "passive"))
    )
    (net (code "43") (name "/TIMER7_CH3") (class "Default")
      (node (ref "SIGNAL") (pin "5") (pinfunction "5_5") (pintype "passive"))
      (node (ref "XP2") (pin "23") (pinfunction "23_23") (pintype "passive"))
    )
    (net (code "44") (name "/UART3_RX") (class "Default")
      (node (ref "UART3") (pin "2") (pinfunction "2_2") (pintype "passive"))
      (node (ref "XP3") (pin "23") (pinfunction "23_23") (pintype "passive"))
    )
    (net (code "45") (name "/UART3_TX") (class "Default")
      (node (ref "UART3") (pin "3") (pinfunction "3_3") (pintype "passive"))
      (node (ref "XP3") (pin "25") (pinfunction "25_25") (pintype "passive"))
    )
    (net (code "46") (name "/UART4_RX") (class "Default")
      (node (ref "UART4") (pin "2") (pinfunction "2_2") (pintype "passive"))
      (node (ref "XP2") (pin "28") (pinfunction "28_28") (pintype "passive"))
    )
    (net (code "47") (name "/UART4_TX") (class "Default")
      (node (ref "UART4") (pin "3") (pinfunction "3_3") (pintype "passive"))
      (node (ref "XP2") (pin "30") (pinfunction "30_30") (pintype "passive"))
    )
    (net (code "48") (name "/USART0_RX") (class "Default")
      (node (ref "USART0") (pin "2") (pinfunction "2_2") (pintype "passive"))
      (node (ref "XP3") (pin "27") (pinfunction "27_27") (pintype "passive"))
    )
    (net (code "49") (name "/USART0_TX") (class "Default")
      (node (ref "USART0") (pin "3") (pinfunction "3_3") (pintype "passive"))
      (node (ref "XP3") (pin "29") (pinfunction "29_29") (pintype "passive"))
    )
    (net (code "50") (name "/USART1_RX") (class "Default")
      (node (ref "USART1") (pin "2") (pinfunction "2_2") (pintype "passive"))
      (node (ref "XP1") (pin "17") (pinfunction "17_17") (pintype "passive"))
    )
    (net (code "51") (name "/USART1_TX") (class "Default")
      (node (ref "USART1") (pin "3") (pinfunction "3_3") (pintype "passive"))
      (node (ref "XP1") (pin "19") (pinfunction "19_19") (pintype "passive"))
    )
    (net (code "52") (name "/USART2_CTS") (class "Default")
      (node (ref "USART2") (pin "4") (pinfunction "4_4") (pintype "passive"))
      (node (ref "XP4") (pin "14") (pinfunction "14_14") (pintype "passive"))
    )
    (net (code "53") (name "/USART2_RTS") (class "Default")
      (node (ref "USART2") (pin "5") (pinfunction "5_5") (pintype "passive"))
      (node (ref "XP4") (pin "16") (pinfunction "16_16") (pintype "passive"))
    )
    (net (code "54") (name "/USART2_RX") (class "Default")
      (node (ref "USART2") (pin "2") (pinfunction "2_2") (pintype "passive"))
      (node (ref "XP4") (pin "10") (pinfunction "10_10") (pintype "passive"))
    )
    (net (code "55") (name "/USART2_TX") (class "Default")
      (node (ref "USART2") (pin "3") (pinfunction "3_3") (pintype "passive"))
      (node (ref "XP4") (pin "12") (pinfunction "12_12") (pintype "passive"))
    )
    (net (code "56") (name "/USART5_RX") (class "Default")
      (node (ref "USART5") (pin "2") (pinfunction "2_2") (pintype "passive"))
      (node (ref "XP4") (pin "22") (pinfunction "22_22") (pintype "passive"))
    )
    (net (code "57") (name "/USART5_TX") (class "Default")
      (node (ref "USART5") (pin "3") (pinfunction "3_3") (pintype "passive"))
      (node (ref "XP4") (pin "24") (pinfunction "24_24") (pintype "passive"))
    )
    (net (code "58") (name "3V3") (class "Default")
      (node (ref "ADC") (pin "1") (pinfunction "1_1") (pintype "passive"))
      (node (ref "C30") (pin "2") (pinfunction "2_2") (pintype "passive"))
      (node (ref "GPIO") (pin "1") (pinfunction "1_1") (pintype "passive"))
      (node (ref "LDO") (pin "3") (pinfunction "OUT_3") (pintype "passive"))
      (node (ref "R35") (pin "2") (pinfunction "2_2") (pintype "passive"))
      (node (ref "S1") (pin "2") (pinfunction "2_2") (pintype "passive"))
      (node (ref "UART3") (pin "1") (pinfunction "1_1") (pintype "passive"))
      (node (ref "UART4") (pin "1") (pinfunction "1_1") (pintype "passive"))
      (node (ref "USART0") (pin "1") (pinfunction "1_1") (pintype "passive"))
      (node (ref "USART1") (pin "1") (pinfunction "1_1") (pintype "passive"))
      (node (ref "USART2") (pin "1") (pinfunction "1_1") (pintype "passive"))
      (node (ref "USART5") (pin "1") (pinfunction "1_1") (pintype "passive"))
      (node (ref "XP1") (pin "10") (pinfunction "10_10") (pintype "passive"))
      (node (ref "XP1") (pin "9") (pinfunction "9_9") (pintype "passive"))
      (node (ref "XP4") (pin "31") (pinfunction "31_31") (pintype "passive"))
      (node (ref "XP4") (pin "32") (pinfunction "32_32") (pintype "passive"))
    )
    (net (code "59") (name "4V2") (class "Default")
      (node (ref "C25") (pin "1") (pinfunction "1_1") (pintype "passive"))
      (node (ref "L3") (pin "2") (pinfunction "2_2") (pintype "passive"))
      (node (ref "R25") (pin "2") (pinfunction "2_2") (pintype "passive"))
      (node (ref "R26") (pin "2") (pinfunction "2_2") (pintype "passive"))
      (node (ref "XP1") (pin "11") (pinfunction "11_11") (pintype "passive"))
      (node (ref "XP1") (pin "12") (pinfunction "12_12") (pintype "passive"))
      (node (ref "XP1") (pin "13") (pinfunction "13_13") (pintype "passive"))
      (node (ref "XP1") (pin "14") (pinfunction "14_14") (pintype "passive"))
      (node (ref "XP4") (pin "27") (pinfunction "27_27") (pintype "passive"))
      (node (ref "XP4") (pin "28") (pinfunction "28_28") (pintype "passive"))
      (node (ref "XP4") (pin "29") (pinfunction "29_29") (pintype "passive"))
      (node (ref "XP4") (pin "30") (pinfunction "30_30") (pintype "passive"))
    )
    (net (code "60") (name "5V") (class "Default")
      (node (ref "AT") (pin "21") (pinfunction "AVDD_21") (pintype "passive"))
      (node (ref "AT") (pin "24") (pinfunction "PVDD_24") (pintype "passive"))
      (node (ref "AT") (pin "3") (pinfunction "DVDD_3") (pintype "passive"))
      (node (ref "C11") (pin "1") (pinfunction "1_1") (pintype "passive"))
      (node (ref "C4") (pin "1") (pinfunction "1_1") (pintype "passive"))
      (node (ref "C6") (pin "1") (pinfunction "1_1") (pintype "passive"))
      (node (ref "C7") (pin "1") (pinfunction "1_1") (pintype "passive"))
      (node (ref "CAN1") (pin "1") (pinfunction "1_1") (pintype "passive"))
      (node (ref "I2C") (pin "1") (pinfunction "1_1") (pintype "passive"))
      (node (ref "IN") (pin "1") (pinfunction "1_1") (pintype "passive"))
      (node (ref "L1") (pin "2") (pinfunction "2_2") (pintype "passive"))
      (node (ref "R1") (pin "2") (pinfunction "2_2") (pintype "passive"))
      (node (ref "R10") (pin "2") (pinfunction "2_2") (pintype "passive"))
      (node (ref "R3") (pin "2") (pinfunction "2_2") (pintype "passive"))
      (node (ref "R36") (pin "2") (pinfunction "2_2") (pintype "passive"))
      (node (ref "R5") (pin "2") (pinfunction "2_2") (pintype "passive"))
      (node (ref "R8") (pin "2") (pinfunction "2_2") (pintype "passive"))
      (node (ref "R9") (pin "2") (pinfunction "2_2") (pintype "passive"))
      (node (ref "SPI") (pin "1") (pinfunction "1_1") (pintype "passive"))
      (node (ref "TYPE-C") (pin "10") (pinfunction "B4_10") (pintype "passive"))
      (node (ref "TYPE-C") (pin "15") (pinfunction "B9_15") (pintype "passive"))
      (node (ref "TYPE-C") (pin "2") (pinfunction "A4_2") (pintype "passive"))
      (node (ref "TYPE-C") (pin "7") (pinfunction "A9_7") (pintype "passive"))
      (node (ref "XP1") (pin "7") (pinfunction "7_7") (pintype "passive"))
      (node (ref "XP1") (pin "8") (pinfunction "8_8") (pintype "passive"))
      (node (ref "XP4") (pin "33") (pinfunction "33_33") (pintype "passive"))
      (node (ref "XP4") (pin "34") (pinfunction "34_34") (pintype "passive"))
    )
    (net (code "61") (name "GND") (class "Default")
      (node (ref "AT") (pin "20") (pinfunction "AGND_20") (pintype "passive"))
      (node (ref "AT") (pin "23") (pinfunction "PGND_23") (pintype "passive"))
      (node (ref "AT") (pin "4") (pinfunction "DGND_4") (pintype "passive"))
      (node (ref "C10") (pin "1") (pinfunction "1_1") (pintype "passive"))
      (node (ref "C11") (pin "2") (pinfunction "2_2") (pintype "passive"))
      (node (ref "C12") (pin "2") (pinfunction "2_2") (pintype "passive"))
      (node (ref "C13") (pin "2") (pinfunction "2_2") (pintype "passive"))
      (node (ref "C14") (pin "1") (pinfunction "1_1") (pintype "passive"))
      (node (ref "C17") (pin "1") (pinfunction "1_1") (pintype "passive"))
      (node (ref "C18") (pin "2") (pinfunction "2_2") (pintype "passive"))
      (node (ref "C19") (pin "2") (pinfunction "2_2") (pintype "passive"))
      (node (ref "C20") (pin "2") (pinfunction "2_2") (pintype "passive"))
      (node (ref "C21") (pin "1") (pinfunction "1_1") (pintype "passive"))
      (node (ref "C24") (pin "1") (pinfunction "1_1") (pintype "passive"))
      (node (ref "C25") (pin "2") (pinfunction "2_2") (pintype "passive"))
      (node (ref "C26") (pin "2") (pinfunction "2_2") (pintype "passive"))
      (node (ref "C27") (pin "2") (pinfunction "2_2") (pintype "passive"))
      (node (ref "C28") (pin "1") (pinfunction "1_1") (pintype "passive"))
      (node (ref "C29") (pin "1") (pinfunction "1_1") (pintype "passive"))
      (node (ref "C30") (pin "1") (pinfunction "1_1") (pintype "passive"))
      (node (ref "C4") (pin "2") (pinfunction "2_2") (pintype "passive"))
      (node (ref "C6") (pin "2") (pinfunction "2_2") (pintype "passive"))
      (node (ref "C7") (pin "2") (pinfunction "2_2") (pintype "passive"))
      (node (ref "CAN1") (pin "4") (pinfunction "4_4") (pintype "passive"))
      (node (ref "D1") (pin "A") (pinfunction "A_A") (pintype "passive"))
      (node (ref "D2") (pin "A") (pinfunction "A_A") (pintype "passive"))
      (node (ref "D3") (pin "A") (pinfunction "A_A") (pintype "passive"))
      (node (ref "DC1") (pin "5") (pinfunction "GND_5") (pintype "passive"))
      (node (ref "DC1") (pin "9") (pinfunction "GND_9") (pintype "passive"))
      (node (ref "DC2") (pin "5") (pinfunction "GND_5") (pintype "passive"))
      (node (ref "DC2") (pin "9") (pinfunction "GND_9") (pintype "passive"))
      (node (ref "DC3") (pin "5") (pinfunction "GND_5") (pintype "passive"))
      (node (ref "DC3") (pin "9") (pinfunction "GND_9") (pintype "passive"))
      (node (ref "GND") (pin "1") (pinfunction "1_1") (pintype "passive"))
      (node (ref "GND") (pin "10") (pinfunction "10_10") (pintype "passive"))
      (node (ref "GND") (pin "11") (pinfunction "11_11") (pintype "passive"))
      (node (ref "GND") (pin "12") (pinfunction "12_12") (pintype "passive"))
      (node (ref "GND") (pin "13") (pinfunction "13_13") (pintype "passive"))
      (node (ref "GND") (pin "2") (pinfunction "2_2") (pintype "passive"))
      (node (ref "GND") (pin "3") (pinfunction "3_3") (pintype "passive"))
      (node (ref "GND") (pin "4") (pinfunction "4_4") (pintype "passive"))
      (node (ref "GND") (pin "5") (pinfunction "5_5") (pintype "passive"))
      (node (ref "GND") (pin "6") (pinfunction "6_6") (pintype "passive"))
      (node (ref "GND") (pin "7") (pinfunction "7_7") (pintype "passive"))
      (node (ref "GND") (pin "8") (pinfunction "8_8") (pintype "passive"))
      (node (ref "GND") (pin "9") (pinfunction "9_9") (pintype "passive"))
      (node (ref "GPIO") (pin "6") (pinfunction "6_6") (pintype "passive"))
      (node (ref "I2C") (pin "4") (pinfunction "4_4") (pintype "passive"))
      (node (ref "IN") (pin "3") (pinfunction "3_3") (pintype "passive"))
      (node (ref "LDO") (pin "2") (pinfunction "GND_2") (pintype "passive"))
      (node (ref "LDO") (pin "4") (pinfunction "GND_4") (pintype "passive"))
      (node (ref "LED1") (pin "2") (pinfunction "К_2") (pintype "passive"))
      (node (ref "LED2") (pin "2") (pinfunction "К_2") (pintype "passive"))
      (node (ref "OUT") (pin "3") (pinfunction "3_3") (pintype "passive"))
      (node (ref "R11") (pin "2") (pinfunction "2_2") (pintype "passive"))
      (node (ref "R15") (pin "2") (pinfunction "2_2") (pintype "passive"))
      (node (ref "R16") (pin "2") (pinfunction "2_2") (pintype "passive"))
      (node (ref "R19") (pin "2") (pinfunction "2_2") (pintype "passive"))
      (node (ref "R2") (pin "2") (pinfunction "2_2") (pintype "passive"))
      (node (ref "R23") (pin "2") (pinfunction "2_2") (pintype "passive"))
      (node (ref "R24") (pin "2") (pinfunction "2_2") (pintype "passive"))
      (node (ref "R27") (pin "2") (pinfunction "2_2") (pintype "passive"))
      (node (ref "R30") (pin "2") (pinfunction "2_2") (pintype "passive"))
      (node (ref "R32") (pin "2") (pinfunction "2_2") (pintype "passive"))
      (node (ref "R33") (pin "2") (pinfunction "2_2") (pintype "passive"))
      (node (ref "R34") (pin "2") (pinfunction "2_2") (pintype "passive"))
      (node (ref "R37") (pin "2") (pinfunction "2_2") (pintype "passive"))
      (node (ref "R39") (pin "1") (pinfunction "1_1") (pintype "passive"))
      (node (ref "R6") (pin "1") (pinfunction "1_1") (pintype "passive"))
      (node (ref "SPI") (pin "7") (pinfunction "7_7") (pintype "passive"))
      (node (ref "TYPE-C") (pin "1") (pinfunction "A1_1") (pintype "passive"))
      (node (ref "TYPE-C") (pin "16") (pinfunction "B12_16") (pintype "passive"))
      (node (ref "TYPE-C") (pin "8") (pinfunction "A12_8") (pintype "passive"))
      (node (ref "TYPE-C") (pin "9") (pinfunction "B1_9") (pintype "passive"))
      (node (ref "UART3") (pin "4") (pinfunction "4_4") (pintype "passive"))
      (node (ref "UART4") (pin "4") (pinfunction "4_4") (pintype "passive"))
      (node (ref "USART0") (pin "4") (pinfunction "4_4") (pintype "passive"))
      (node (ref "USART1") (pin "4") (pinfunction "4_4") (pintype "passive"))
      (node (ref "USART2") (pin "6") (pinfunction "6_6") (pintype "passive"))
      (node (ref "USART5") (pin "4") (pinfunction "4_4") (pintype "passive"))
      (node (ref "XP1") (pin "37") (pinfunction "37_37") (pintype "passive"))
      (node (ref "XP1") (pin "38") (pinfunction "38_38") (pintype "passive"))
      (node (ref "XP1") (pin "39") (pinfunction "39_39") (pintype "passive"))
      (node (ref "XP1") (pin "40") (pinfunction "40_40") (pintype "passive"))
      (node (ref "XP2") (pin "1") (pinfunction "1_1") (pintype "passive"))
      (node (ref "XP2") (pin "2") (pinfunction "2_2") (pintype "passive"))
      (node (ref "XP2") (pin "3") (pinfunction "3_3") (pintype "passive"))
      (node (ref "XP2") (pin "37") (pinfunction "37_37") (pintype "passive"))
      (node (ref "XP2") (pin "38") (pinfunction "38_38") (pintype "passive"))
      (node (ref "XP2") (pin "39") (pinfunction "39_39") (pintype "passive"))
      (node (ref "XP2") (pin "4") (pinfunction "4_4") (pintype "passive"))
      (node (ref "XP2") (pin "40") (pinfunction "40_40") (pintype "passive"))
      (node (ref "XP2") (pin "5") (pinfunction "5_5") (pintype "passive"))
      (node (ref "XP2") (pin "6") (pinfunction "6_6") (pintype "passive"))
      (node (ref "XP3") (pin "1") (pinfunction "1_1") (pintype "passive"))
      (node (ref "XP3") (pin "2") (pinfunction "2_2") (pintype "passive"))
      (node (ref "XP3") (pin "3") (pinfunction "3_3") (pintype "passive"))
      (node (ref "XP3") (pin "35") (pinfunction "35_35") (pintype "passive"))
      (node (ref "XP3") (pin "36") (pinfunction "36_36") (pintype "passive"))
      (node (ref "XP3") (pin "37") (pinfunction "37_37") (pintype "passive"))
      (node (ref "XP3") (pin "38") (pinfunction "38_38") (pintype "passive"))
      (node (ref "XP3") (pin "39") (pinfunction "39_39") (pintype "passive"))
      (node (ref "XP3") (pin "4") (pinfunction "4_4") (pintype "passive"))
      (node (ref "XP3") (pin "40") (pinfunction "40_40") (pintype "passive"))
      (node (ref "XP4") (pin "1") (pinfunction "1_1") (pintype "passive"))
      (node (ref "XP4") (pin "2") (pinfunction "2_2") (pintype "passive"))
      (node (ref "XP4") (pin "3") (pinfunction "3_3") (pintype "passive"))
      (node (ref "XP4") (pin "4") (pinfunction "4_4") (pintype "passive"))
      (node (ref "XT1") (pin "2") (pinfunction "NEG_2") (pintype "passive"))
    )
    (net (code "62") (name "Net-(AT-CLKIN)") (class "Default")
      (node (ref "AT") (pin "5") (pinfunction "CLKIN_5") (pintype "passive"))
      (node (ref "Y1") (pin "2") (pinfunction "2_2") (pintype "passive"))
    )
    (net (code "63") (name "Net-(AT-HSYNC)") (class "Default")
      (node (ref "AT") (pin "18") (pinfunction "HSYNC_18") (pintype "passive"))
      (node (ref "R5") (pin "1") (pinfunction "1_1") (pintype "passive"))
    )
    (net (code "64") (name "Net-(AT-LOS)") (class "Default")
      (node (ref "AT") (pin "12") (pinfunction "LOS_12") (pintype "passive"))
      (node (ref "R1") (pin "1") (pinfunction "1_1") (pintype "passive"))
    )
    (net (code "65") (name "Net-(AT-RESET)") (class "Default")
      (node (ref "AT") (pin "19") (pinfunction "RESET_19") (pintype "passive"))
      (node (ref "R8") (pin "1") (pinfunction "1_1") (pintype "passive"))
    )
    (net (code "66") (name "Net-(AT-SAG)") (class "Default")
      (node (ref "AT") (pin "25") (pinfunction "SAG_25") (pintype "passive"))
      (node (ref "C3") (pin "1") (pinfunction "1_1") (pintype "passive"))
    )
    (net (code "67") (name "Net-(AT-VIN)") (class "Default")
      (node (ref "AT") (pin "22") (pinfunction "VIN_22") (pintype "passive"))
      (node (ref "C1") (pin "1") (pinfunction "1_1") (pintype "passive"))
      (node (ref "R6") (pin "2") (pinfunction "2_2") (pintype "passive"))
    )
    (net (code "68") (name "Net-(AT-VOUT)") (class "Default")
      (node (ref "AT") (pin "26") (pinfunction "VOUT_26") (pintype "passive"))
      (node (ref "C5") (pin "1") (pinfunction "1_1") (pintype "passive"))
    )
    (net (code "69") (name "Net-(AT-VSYNC)") (class "Default")
      (node (ref "AT") (pin "17") (pinfunction "VSYNC_17") (pintype "passive"))
      (node (ref "R3") (pin "1") (pinfunction "1_1") (pintype "passive"))
    )
    (net (code "70") (name "Net-(AT-XFB)") (class "Default")
      (node (ref "AT") (pin "6") (pinfunction "XFB_6") (pintype "passive"))
      (node (ref "Y1") (pin "1") (pinfunction "1_1") (pintype "passive"))
    )
    (net (code "71") (name "Net-(C3-Pad2)") (class "Default")
      (node (ref "C3") (pin "2") (pinfunction "2_2") (pintype "passive"))
      (node (ref "C5") (pin "2") (pinfunction "2_2") (pintype "passive"))
      (node (ref "R7") (pin "1") (pinfunction "1_1") (pintype "passive"))
    )
    (net (code "72") (name "Net-(C8-Pad1)") (class "Default")
      (node (ref "C8") (pin "1") (pinfunction "1_1") (pintype "passive"))
      (node (ref "R9") (pin "1") (pinfunction "1_1") (pintype "passive"))
    )
    (net (code "73") (name "Net-(C9-Pad1)") (class "Default")
      (node (ref "C9") (pin "1") (pinfunction "1_1") (pintype "passive"))
      (node (ref "R12") (pin "1") (pinfunction "1_1") (pintype "passive"))
    )
    (net (code "74") (name "Net-(C12-Pad1)") (class "Default")
      (node (ref "C12") (pin "1") (pinfunction "1_1") (pintype "passive"))
      (node (ref "R13") (pin "1") (pinfunction "1_1") (pintype "passive"))
    )
    (net (code "75") (name "Net-(C15-Pad1)") (class "Default")
      (node (ref "C15") (pin "1") (pinfunction "1_1") (pintype "passive"))
      (node (ref "R17") (pin "1") (pinfunction "1_1") (pintype "passive"))
    )
    (net (code "76") (name "Net-(C16-Pad1)") (class "Default")
      (node (ref "C16") (pin "1") (pinfunction "1_1") (pintype "passive"))
      (node (ref "R20") (pin "1") (pinfunction "1_1") (pintype "passive"))
    )
    (net (code "77") (name "Net-(C19-Pad1)") (class "Default")
      (node (ref "C19") (pin "1") (pinfunction "1_1") (pintype "passive"))
      (node (ref "R21") (pin "1") (pinfunction "1_1") (pintype "passive"))
    )
    (net (code "78") (name "Net-(C22-Pad1)") (class "Default")
      (node (ref "C22") (pin "1") (pinfunction "1_1") (pintype "passive"))
      (node (ref "R25") (pin "1") (pinfunction "1_1") (pintype "passive"))
    )
    (net (code "79") (name "Net-(C23-Pad1)") (class "Default")
      (node (ref "C23") (pin "1") (pinfunction "1_1") (pintype "passive"))
      (node (ref "R28") (pin "1") (pinfunction "1_1") (pintype "passive"))
    )
    (net (code "80") (name "Net-(C26-Pad1)") (class "Default")
      (node (ref "C26") (pin "1") (pinfunction "1_1") (pintype "passive"))
      (node (ref "R29") (pin "1") (pinfunction "1_1") (pintype "passive"))
    )
    (net (code "81") (name "Net-(DC1-BST)") (class "Default")
      (node (ref "DC1") (pin "8") (pinfunction "BST_8") (pintype "passive"))
      (node (ref "R12") (pin "2") (pinfunction "2_2") (pintype "passive"))
    )
    (net (code "82") (name "Net-(DC1-COMP)") (class "Default")
      (node (ref "C13") (pin "1") (pinfunction "1_1") (pintype "passive"))
      (node (ref "DC1") (pin "3") (pinfunction "COMP_3") (pintype "passive"))
      (node (ref "R13") (pin "2") (pinfunction "2_2") (pintype "passive"))
    )
    (net (code "83") (name "Net-(DC1-EN)") (class "Default")
      (node (ref "DC1") (pin "2") (pinfunction "EN_2") (pintype "passive"))
      (node (ref "R14") (pin "1") (pinfunction "1_1") (pintype "passive"))
      (node (ref "R15") (pin "1") (pinfunction "1_1") (pintype "passive"))
    )
    (net (code "84") (name "Net-(DC1-FB)") (class "Default")
      (node (ref "C8") (pin "2") (pinfunction "2_2") (pintype "passive"))
      (node (ref "DC1") (pin "4") (pinfunction "FB_4") (pintype "passive"))
      (node (ref "R10") (pin "1") (pinfunction "1_1") (pintype "passive"))
      (node (ref "R11") (pin "1") (pinfunction "1_1") (pintype "passive"))
    )
    (net (code "85") (name "Net-(DC1-FREQ)") (class "Default")
      (node (ref "DC1") (pin "6") (pinfunction "FREQ_6") (pintype "passive"))
      (node (ref "R16") (pin "1") (pinfunction "1_1") (pintype "passive"))
    )
    (net (code "86") (name "Net-(DC1-SW)") (class "Default")
      (node (ref "C9") (pin "2") (pinfunction "2_2") (pintype "passive"))
      (node (ref "D1") (pin "C") (pinfunction "C_C") (pintype "passive"))
      (node (ref "DC1") (pin "1") (pinfunction "SW_1") (pintype "passive"))
      (node (ref "L1") (pin "1") (pinfunction "1_1") (pintype "passive"))
    )
    (net (code "87") (name "Net-(DC2-BST)") (class "Default")
      (node (ref "DC2") (pin "8") (pinfunction "BST_8") (pintype "passive"))
      (node (ref "R20") (pin "2") (pinfunction "2_2") (pintype "passive"))
    )
    (net (code "88") (name "Net-(DC2-COMP)") (class "Default")
      (node (ref "C20") (pin "1") (pinfunction "1_1") (pintype "passive"))
      (node (ref "DC2") (pin "3") (pinfunction "COMP_3") (pintype "passive"))
      (node (ref "R21") (pin "2") (pinfunction "2_2") (pintype "passive"))
    )
    (net (code "89") (name "Net-(DC2-EN)") (class "Default")
      (node (ref "DC2") (pin "2") (pinfunction "EN_2") (pintype "passive"))
      (node (ref "R22") (pin "1") (pinfunction "1_1") (pintype "passive"))
      (node (ref "R23") (pin "1") (pinfunction "1_1") (pintype "passive"))
    )
    (net (code "90") (name "Net-(DC2-FB)") (class "Default")
      (node (ref "C15") (pin "2") (pinfunction "2_2") (pintype "passive"))
      (node (ref "DC2") (pin "4") (pinfunction "FB_4") (pintype "passive"))
      (node (ref "R18") (pin "1") (pinfunction "1_1") (pintype "passive"))
      (node (ref "R19") (pin "1") (pinfunction "1_1") (pintype "passive"))
    )
    (net (code "91") (name "Net-(DC2-FREQ)") (class "Default")
      (node (ref "DC2") (pin "6") (pinfunction "FREQ_6") (pintype "passive"))
      (node (ref "R24") (pin "1") (pinfunction "1_1") (pintype "passive"))
    )
    (net (code "92") (name "Net-(DC2-SW)") (class "Default")
      (node (ref "C16") (pin "2") (pinfunction "2_2") (pintype "passive"))
      (node (ref "D2") (pin "C") (pinfunction "C_C") (pintype "passive"))
      (node (ref "DC2") (pin "1") (pinfunction "SW_1") (pintype "passive"))
      (node (ref "L2") (pin "1") (pinfunction "1_1") (pintype "passive"))
    )
    (net (code "93") (name "Net-(DC3-BST)") (class "Default")
      (node (ref "DC3") (pin "8") (pinfunction "BST_8") (pintype "passive"))
      (node (ref "R28") (pin "2") (pinfunction "2_2") (pintype "passive"))
    )
    (net (code "94") (name "Net-(DC3-COMP)") (class "Default")
      (node (ref "C27") (pin "1") (pinfunction "1_1") (pintype "passive"))
      (node (ref "DC3") (pin "3") (pinfunction "COMP_3") (pintype "passive"))
      (node (ref "R29") (pin "2") (pinfunction "2_2") (pintype "passive"))
    )
    (net (code "95") (name "Net-(DC3-EN)") (class "Default")
      (node (ref "DC3") (pin "2") (pinfunction "EN_2") (pintype "passive"))
      (node (ref "R31") (pin "1") (pinfunction "1_1") (pintype "passive"))
      (node (ref "R32") (pin "1") (pinfunction "1_1") (pintype "passive"))
    )
    (net (code "96") (name "Net-(DC3-FB)") (class "Default")
      (node (ref "C22") (pin "2") (pinfunction "2_2") (pintype "passive"))
      (node (ref "DC3") (pin "4") (pinfunction "FB_4") (pintype "passive"))
      (node (ref "R26") (pin "1") (pinfunction "1_1") (pintype "passive"))
      (node (ref "R27") (pin "1") (pinfunction "1_1") (pintype "passive"))
    )
    (net (code "97") (name "Net-(DC3-FREQ)") (class "Default")
      (node (ref "DC3") (pin "6") (pinfunction "FREQ_6") (pintype "passive"))
      (node (ref "R33") (pin "1") (pinfunction "1_1") (pintype "passive"))
    )
    (net (code "98") (name "Net-(DC3-SW)") (class "Default")
      (node (ref "C23") (pin "2") (pinfunction "2_2") (pintype "passive"))
      (node (ref "D3") (pin "C") (pinfunction "C_C") (pintype "passive"))
      (node (ref "DC3") (pin "1") (pinfunction "SW_1") (pintype "passive"))
      (node (ref "L3") (pin "1") (pinfunction "1_1") (pintype "passive"))
    )
    (net (code "99") (name "Net-(LED1-А)") (class "Default")
      (node (ref "LED1") (pin "1") (pinfunction "А_1") (pintype "passive"))
      (node (ref "R36") (pin "1") (pinfunction "1_1") (pintype "passive"))
    )
    (net (code "100") (name "Net-(LED2-А)") (class "Default")
      (node (ref "LED2") (pin "1") (pinfunction "А_1") (pintype "passive"))
      (node (ref "R35") (pin "1") (pinfunction "1_1") (pintype "passive"))
    )
    (net (code "101") (name "Net-(TYPE-C-A5)") (class "Default")
      (node (ref "R30") (pin "1") (pinfunction "1_1") (pintype "passive"))
      (node (ref "TYPE-C") (pin "3") (pinfunction "A5_3") (pintype "passive"))
    )
    (net (code "102") (name "Net-(TYPE-C-B5)") (class "Default")
      (node (ref "R34") (pin "1") (pinfunction "1_1") (pintype "passive"))
      (node (ref "TYPE-C") (pin "11") (pinfunction "B5_11") (pintype "passive"))
    )
    (net (code "103") (name "Net-(XT2-NEG)") (class "Default")
      (node (ref "R37") (pin "1") (pinfunction "1_1") (pintype "passive"))
      (node (ref "R38") (pin "2") (pinfunction "2_2") (pintype "passive"))
      (node (ref "XT2") (pin "2") (pinfunction "NEG_2") (pintype "passive"))
    )
    (net (code "104") (name "SERVO") (class "Default")
      (node (ref "C18") (pin "1") (pinfunction "1_1") (pintype "passive"))
      (node (ref "L2") (pin "2") (pinfunction "2_2") (pintype "passive"))
      (node (ref "R17") (pin "2") (pinfunction "2_2") (pintype "passive"))
      (node (ref "R18") (pin "2") (pinfunction "2_2") (pintype "passive"))
      (node (ref "VCC") (pin "1") (pinfunction "1_1") (pintype "passive"))
      (node (ref "VCC") (pin "10") (pinfunction "10_10") (pintype "passive"))
      (node (ref "VCC") (pin "11") (pinfunction "11_11") (pintype "passive"))
      (node (ref "VCC") (pin "12") (pinfunction "12_12") (pintype "passive"))
      (node (ref "VCC") (pin "13") (pinfunction "13_13") (pintype "passive"))
      (node (ref "VCC") (pin "2") (pinfunction "2_2") (pintype "passive"))
      (node (ref "VCC") (pin "3") (pinfunction "3_3") (pintype "passive"))
      (node (ref "VCC") (pin "4") (pinfunction "4_4") (pintype "passive"))
      (node (ref "VCC") (pin "5") (pinfunction "5_5") (pintype "passive"))
      (node (ref "VCC") (pin "6") (pinfunction "6_6") (pintype "passive"))
      (node (ref "VCC") (pin "7") (pinfunction "7_7") (pintype "passive"))
      (node (ref "VCC") (pin "8") (pinfunction "8_8") (pintype "passive"))
      (node (ref "VCC") (pin "9") (pinfunction "9_9") (pintype "passive"))
    )
    (net (code "105") (name "VCC") (class "Default")
      (node (ref "C10") (pin "2") (pinfunction "2_2") (pintype "passive"))
      (node (ref "C14") (pin "2") (pinfunction "2_2") (pintype "passive"))
      (node (ref "C17") (pin "2") (pinfunction "2_2") (pintype "passive"))
      (node (ref "C2") (pin "1") (pinfunction "1_1") (pintype "passive"))
      (node (ref "C21") (pin "2") (pinfunction "2_2") (pintype "passive"))
      (node (ref "C24") (pin "2") (pinfunction "2_2") (pintype "passive"))
      (node (ref "C28") (pin "2") (pinfunction "2_2") (pintype "passive"))
      (node (ref "C29") (pin "2") (pinfunction "2_2") (pintype "passive"))
      (node (ref "C31") (pin "1") (pinfunction "1_1") (pintype "passive"))
      (node (ref "DC1") (pin "7") (pinfunction "VIN_7") (pintype "passive"))
      (node (ref "DC2") (pin "7") (pinfunction "VIN_7") (pintype "passive"))
      (node (ref "DC3") (pin "7") (pinfunction "VIN_7") (pintype "passive"))
      (node (ref "LDO") (pin "1") (pinfunction "INP_1") (pintype "passive"))
      (node (ref "OUT") (pin "1") (pinfunction "1_1") (pintype "passive"))
      (node (ref "R14") (pin "2") (pinfunction "2_2") (pintype "passive"))
      (node (ref "R22") (pin "2") (pinfunction "2_2") (pintype "passive"))
      (node (ref "R31") (pin "2") (pinfunction "2_2") (pintype "passive"))
      (node (ref "R4") (pin "2") (pinfunction "2_2") (pintype "passive"))
      (node (ref "VD1") (pin "2") (pinfunction "К_2") (pintype "passive"))
      (node (ref "XP1") (pin "1") (pinfunction "1_1") (pintype "passive"))
      (node (ref "XP1") (pin "2") (pinfunction "2_2") (pintype "passive"))
      (node (ref "XP1") (pin "3") (pinfunction "3_3") (pintype "passive"))
      (node (ref "XP1") (pin "4") (pinfunction "4_4") (pintype "passive"))
      (node (ref "XP1") (pin "5") (pinfunction "5_5") (pintype "passive"))
      (node (ref "XP1") (pin "6") (pinfunction "6_6") (pintype "passive"))
      (node (ref "XP4") (pin "35") (pinfunction "35_35") (pintype "passive"))
      (node (ref "XP4") (pin "36") (pinfunction "36_36") (pintype "passive"))
      (node (ref "XP4") (pin "37") (pinfunction "37_37") (pintype "passive"))
      (node (ref "XP4") (pin "38") (pinfunction "38_38") (pintype "passive"))
      (node (ref "XP4") (pin "39") (pinfunction "39_39") (pintype "passive"))
      (node (ref "XP4") (pin "40") (pinfunction "40_40") (pintype "passive"))
      (node (ref "XT1") (pin "1") (pinfunction "POS_1") (pintype "passive"))
      (node (ref "XT2") (pin "1") (pinfunction "POS_1") (pintype "passive"))
    )
    (net (code "106") (name "unconnected-(AT-CLKOUT-Pad7)") (class "Default")
      (node (ref "AT") (pin "7") (pinfunction "CLKOUT_7") (pintype "passive"))
    )
    (net (code "107") (name "unconnected-(AT-NC-Pad1)") (class "Default")
      (node (ref "AT") (pin "1") (pinfunction "NC_1") (pintype "passive"))
    )
    (net (code "108") (name "unconnected-(AT-NC-Pad2)") (class "Default")
      (node (ref "AT") (pin "2") (pinfunction "NC_2") (pintype "passive"))
    )
    (net (code "109") (name "unconnected-(AT-NC-Pad13)") (class "Default")
      (node (ref "AT") (pin "13") (pinfunction "NC_13") (pintype "passive"))
    )
    (net (code "110") (name "unconnected-(AT-NC-Pad14)") (class "Default")
      (node (ref "AT") (pin "14") (pinfunction "NC_14") (pintype "passive"))
    )
    (net (code "111") (name "unconnected-(AT-NC-Pad15)") (class "Default")
      (node (ref "AT") (pin "15") (pinfunction "NC_15") (pintype "passive"))
    )
    (net (code "112") (name "unconnected-(AT-NC-Pad16)") (class "Default")
      (node (ref "AT") (pin "16") (pinfunction "NC_16") (pintype "passive"))
    )
    (net (code "113") (name "unconnected-(AT-NC-Pad27)") (class "Default")
      (node (ref "AT") (pin "27") (pinfunction "NC_27") (pintype "passive"))
    )
    (net (code "114") (name "unconnected-(AT-NC-Pad28)") (class "Default")
      (node (ref "AT") (pin "28") (pinfunction "NC_28") (pintype "passive"))
    )
    (net (code "115") (name "unconnected-(TYPE-C-A6-Pad4)") (class "Default")
      (node (ref "TYPE-C") (pin "4") (pinfunction "A6_4") (pintype "passive"))
    )
    (net (code "116") (name "unconnected-(TYPE-C-A7-Pad5)") (class "Default")
      (node (ref "TYPE-C") (pin "5") (pinfunction "A7_5") (pintype "passive"))
    )
    (net (code "117") (name "unconnected-(TYPE-C-A8-Pad6)") (class "Default")
      (node (ref "TYPE-C") (pin "6") (pinfunction "A8_6") (pintype "passive"))
    )
    (net (code "118") (name "unconnected-(TYPE-C-B6-Pad12)") (class "Default")
      (node (ref "TYPE-C") (pin "12") (pinfunction "B6_12") (pintype "passive"))
    )
    (net (code "119") (name "unconnected-(TYPE-C-B7-Pad13)") (class "Default")
      (node (ref "TYPE-C") (pin "13") (pinfunction "B7_13") (pintype "passive"))
    )
    (net (code "120") (name "unconnected-(TYPE-C-B8-Pad14)") (class "Default")
      (node (ref "TYPE-C") (pin "14") (pinfunction "B8_14") (pintype "passive"))
    )
    (net (code "121") (name "unconnected-(XP1-Pad15)") (class "Default")
      (node (ref "XP1") (pin "15") (pinfunction "15_15") (pintype "passive"))
    )
    (net (code "122") (name "unconnected-(XP1-Pad16)") (class "Default")
      (node (ref "XP1") (pin "16") (pinfunction "16_16") (pintype "passive"))
    )
    (net (code "123") (name "unconnected-(XP1-Pad18)") (class "Default")
      (node (ref "XP1") (pin "18") (pinfunction "18_18") (pintype "passive"))
    )
    (net (code "124") (name "unconnected-(XP1-Pad20)") (class "Default")
      (node (ref "XP1") (pin "20") (pinfunction "20_20") (pintype "passive"))
    )
    (net (code "125") (name "unconnected-(XP1-Pad21)") (class "Default")
      (node (ref "XP1") (pin "21") (pinfunction "21_21") (pintype "passive"))
    )
    (net (code "126") (name "unconnected-(XP1-Pad22)") (class "Default")
      (node (ref "XP1") (pin "22") (pinfunction "22_22") (pintype "passive"))
    )
    (net (code "127") (name "unconnected-(XP1-Pad23)") (class "Default")
      (node (ref "XP1") (pin "23") (pinfunction "23_23") (pintype "passive"))
    )
    (net (code "128") (name "unconnected-(XP1-Pad24)") (class "Default")
      (node (ref "XP1") (pin "24") (pinfunction "24_24") (pintype "passive"))
    )
    (net (code "129") (name "unconnected-(XP1-Pad26)") (class "Default")
      (node (ref "XP1") (pin "26") (pinfunction "26_26") (pintype "passive"))
    )
    (net (code "130") (name "unconnected-(XP1-Pad28)") (class "Default")
      (node (ref "XP1") (pin "28") (pinfunction "28_28") (pintype "passive"))
    )
    (net (code "131") (name "unconnected-(XP1-Pad30)") (class "Default")
      (node (ref "XP1") (pin "30") (pinfunction "30_30") (pintype "passive"))
    )
    (net (code "132") (name "unconnected-(XP1-Pad32)") (class "Default")
      (node (ref "XP1") (pin "32") (pinfunction "32_32") (pintype "passive"))
    )
    (net (code "133") (name "unconnected-(XP1-Pad34)") (class "Default")
      (node (ref "XP1") (pin "34") (pinfunction "34_34") (pintype "passive"))
    )
    (net (code "134") (name "unconnected-(XP1-Pad35)") (class "Default")
      (node (ref "XP1") (pin "35") (pinfunction "35_35") (pintype "passive"))
    )
    (net (code "135") (name "unconnected-(XP1-Pad36)") (class "Default")
      (node (ref "XP1") (pin "36") (pinfunction "36_36") (pintype "passive"))
    )
    (net (code "136") (name "unconnected-(XP2-Pad22)") (class "Default")
      (node (ref "XP2") (pin "22") (pinfunction "22_22") (pintype "passive"))
    )
    (net (code "137") (name "unconnected-(XP2-Pad32)") (class "Default")
      (node (ref "XP2") (pin "32") (pinfunction "32_32") (pintype "passive"))
    )
    (net (code "138") (name "unconnected-(XP2-Pad33)") (class "Default")
      (node (ref "XP2") (pin "33") (pinfunction "33_33") (pintype "passive"))
    )
    (net (code "139") (name "unconnected-(XP2-Pad34)") (class "Default")
      (node (ref "XP2") (pin "34") (pinfunction "34_34") (pintype "passive"))
    )
    (net (code "140") (name "unconnected-(XP2-Pad35)") (class "Default")
      (node (ref "XP2") (pin "35") (pinfunction "35_35") (pintype "passive"))
    )
    (net (code "141") (name "unconnected-(XP2-Pad36)") (class "Default")
      (node (ref "XP2") (pin "36") (pinfunction "36_36") (pintype "passive"))
    )
    (net (code "142") (name "unconnected-(XP3-Pad5)") (class "Default")
      (node (ref "XP3") (pin "5") (pinfunction "5_5") (pintype "passive"))
    )
    (net (code "143") (name "unconnected-(XP3-Pad7)") (class "Default")
      (node (ref "XP3") (pin "7") (pinfunction "7_7") (pintype "passive"))
    )
    (net (code "144") (name "unconnected-(XP3-Pad13)") (class "Default")
      (node (ref "XP3") (pin "13") (pinfunction "13_13") (pintype "passive"))
    )
    (net (code "145") (name "unconnected-(XP3-Pad15)") (class "Default")
      (node (ref "XP3") (pin "15") (pinfunction "15_15") (pintype "passive"))
    )
    (net (code "146") (name "unconnected-(XP3-Pad16)") (class "Default")
      (node (ref "XP3") (pin "16") (pinfunction "16_16") (pintype "passive"))
    )
    (net (code "147") (name "unconnected-(XP3-Pad17)") (class "Default")
      (node (ref "XP3") (pin "17") (pinfunction "17_17") (pintype "passive"))
    )
    (net (code "148") (name "unconnected-(XP3-Pad18)") (class "Default")
      (node (ref "XP3") (pin "18") (pinfunction "18_18") (pintype "passive"))
    )
    (net (code "149") (name "unconnected-(XP3-Pad19)") (class "Default")
      (node (ref "XP3") (pin "19") (pinfunction "19_19") (pintype "passive"))
    )
    (net (code "150") (name "unconnected-(XP3-Pad20)") (class "Default")
      (node (ref "XP3") (pin "20") (pinfunction "20_20") (pintype "passive"))
    )
    (net (code "151") (name "unconnected-(XP3-Pad21)") (class "Default")
      (node (ref "XP3") (pin "21") (pinfunction "21_21") (pintype "passive"))
    )
    (net (code "152") (name "unconnected-(XP3-Pad22)") (class "Default")
      (node (ref "XP3") (pin "22") (pinfunction "22_22") (pintype "passive"))
    )
    (net (code "153") (name "unconnected-(XP3-Pad31)") (class "Default")
      (node (ref "XP3") (pin "31") (pinfunction "31_31") (pintype "passive"))
    )
    (net (code "154") (name "unconnected-(XP3-Pad33)") (class "Default")
      (node (ref "XP3") (pin "33") (pinfunction "33_33") (pintype "passive"))
    )
    (net (code "155") (name "unconnected-(XP3-Pad34)") (class "Default")
      (node (ref "XP3") (pin "34") (pinfunction "34_34") (pintype "passive"))
    )
    (net (code "156") (name "unconnected-(XP4-Pad5)") (class "Default")
      (node (ref "XP4") (pin "5") (pinfunction "5_5") (pintype "passive"))
    )
    (net (code "157") (name "unconnected-(XP4-Pad6)") (class "Default")
      (node (ref "XP4") (pin "6") (pinfunction "6_6") (pintype "passive"))
    )
    (net (code "158") (name "unconnected-(XP4-Pad7)") (class "Default")
      (node (ref "XP4") (pin "7") (pinfunction "7_7") (pintype "passive"))
    )
    (net (code "159") (name "unconnected-(XP4-Pad8)") (class "Default")
      (node (ref "XP4") (pin "8") (pinfunction "8_8") (pintype "passive"))
    )
    (net (code "160") (name "unconnected-(XP4-Pad9)") (class "Default")
      (node (ref "XP4") (pin "9") (pinfunction "9_9") (pintype "passive"))
    )
    (net (code "161") (name "unconnected-(XP4-Pad11)") (class "Default")
      (node (ref "XP4") (pin "11") (pinfunction "11_11") (pintype "passive"))
    )
    (net (code "162") (name "unconnected-(XP4-Pad13)") (class "Default")
      (node (ref "XP4") (pin "13") (pinfunction "13_13") (pintype "passive"))
    )
    (net (code "163") (name "unconnected-(XP4-Pad18)") (class "Default")
      (node (ref "XP4") (pin "18") (pinfunction "18_18") (pintype "passive"))
    )
    (net (code "164") (name "unconnected-(XP4-Pad19)") (class "Default")
      (node (ref "XP4") (pin "19") (pinfunction "19_19") (pintype "passive"))
    )
    (net (code "165") (name "unconnected-(XP4-Pad20)") (class "Default")
      (node (ref "XP4") (pin "20") (pinfunction "20_20") (pintype "passive"))
    )
    (net (code "166") (name "unconnected-(XP4-Pad21)") (class "Default")
      (node (ref "XP4") (pin "21") (pinfunction "21_21") (pintype "passive"))
    )
    (net (code "167") (name "unconnected-(XP4-Pad23)") (class "Default")
      (node (ref "XP4") (pin "23") (pinfunction "23_23") (pintype "passive"))
    )
    (net (code "168") (name "unconnected-(XP4-Pad25)") (class "Default")
      (node (ref "XP4") (pin "25") (pinfunction "25_25") (pintype "passive"))
    )
    (net (code "169") (name "unconnected-(XP4-Pad26)") (class "Default")
      (node (ref "XP4") (pin "26") (pinfunction "26_26") (pintype "passive"))
    )
  )
)
